# FPGA_CorePeripherals.net
KiCad netlist of a schematic drawn in Altium Designer
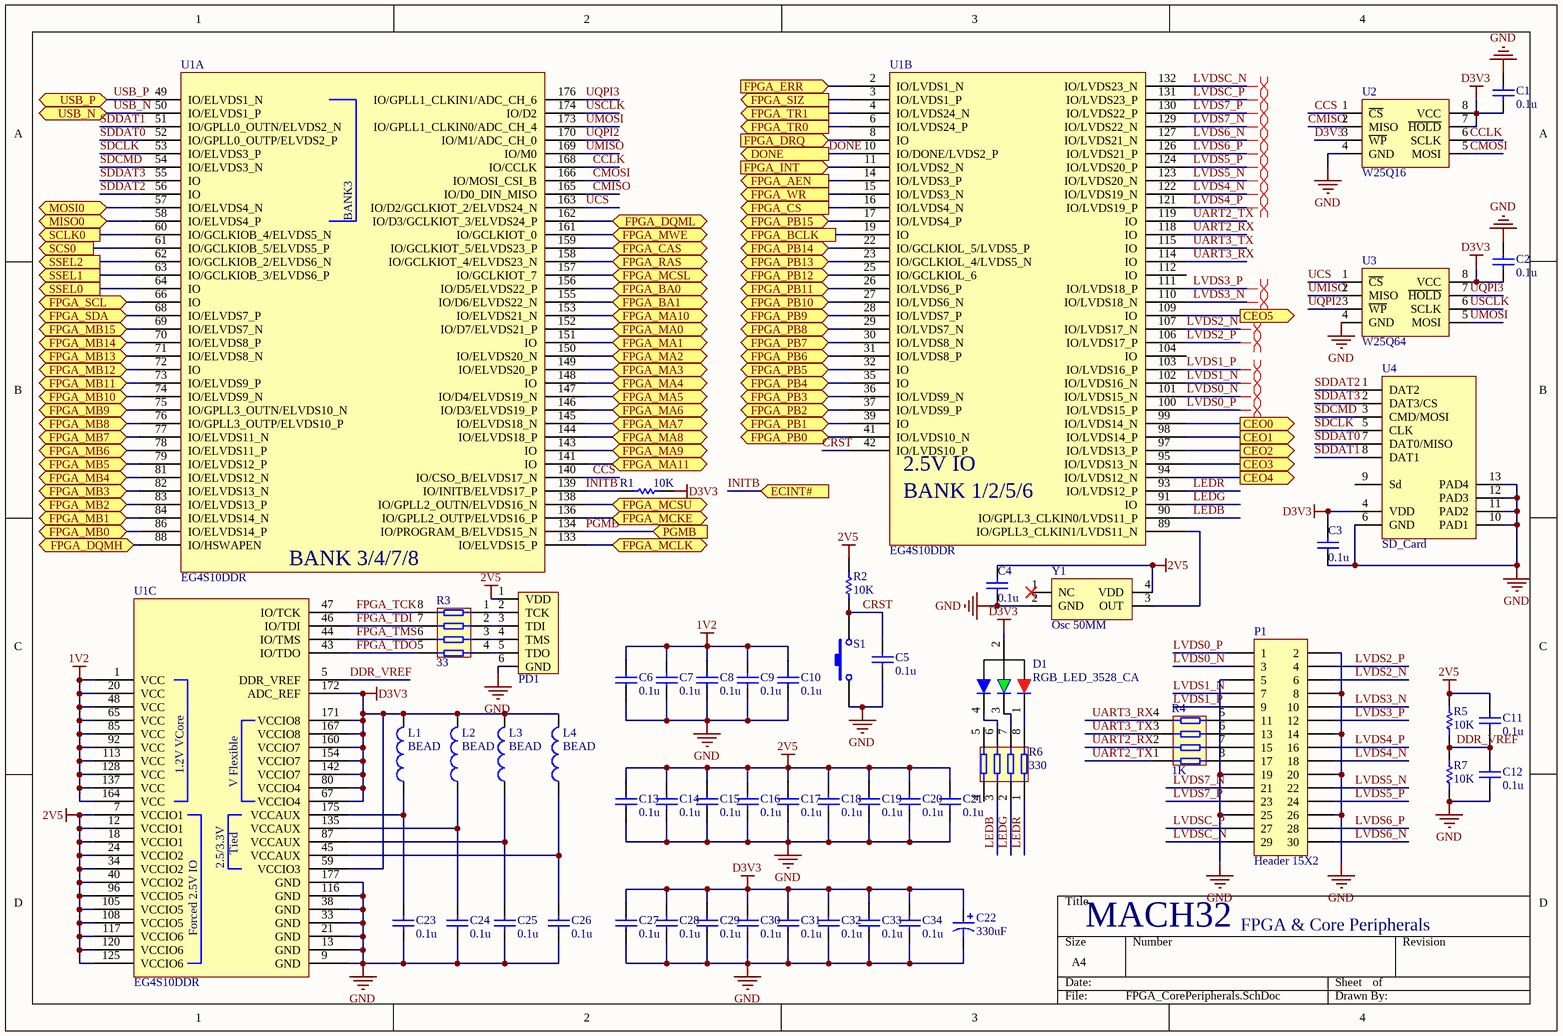
[diagram p0: FPGA_CorePeripherals.SchDoc]

(export (version "E")
  (design (tool "Eeschema 10.0.6"))
  (components
    (comp (ref "C1")
      (value "0.1u")
      (footprint "0603C")
      (description "Capacitor")
      (fields (field (name "Comment") "Cap") (field (name "PUBLISHER") "Altium Limited"))
      (libsource (lib "Miscellaneous Devices") (part "Cap"))
    )
    (comp (ref "C2")
      (value "0.1u")
      (footprint "0603C")
      (description "Capacitor")
      (fields (field (name "Comment") "Cap") (field (name "PUBLISHER") "Altium Limited"))
      (libsource (lib "Miscellaneous Devices") (part "Cap"))
    )
    (comp (ref "C3")
      (value "0.1u")
      (footprint "0603C")
      (description "Capacitor")
      (fields (field (name "Comment") "Cap") (field (name "PUBLISHER") "Altium Limited"))
      (libsource (lib "Miscellaneous Devices") (part "Cap"))
    )
    (comp (ref "C4")
      (value "0.1u")
      (footprint "0603C")
      (description "Capacitor")
      (fields (field (name "Comment") "Cap") (field (name "PUBLISHER") "Altium Limited"))
      (libsource (lib "Miscellaneous Devices") (part "Cap"))
    )
    (comp (ref "C5")
      (value "0.1u")
      (footprint "0603C")
      (description "Capacitor")
      (fields (field (name "Comment") "Cap") (field (name "PUBLISHER") "Altium Limited"))
      (libsource (lib "Miscellaneous Devices") (part "Cap"))
    )
    (comp (ref "C6")
      (value "0.1u")
      (footprint "0603C")
      (description "Capacitor")
      (fields (field (name "Comment") "Cap") (field (name "PUBLISHER") "Altium Limited"))
      (libsource (lib "Miscellaneous Devices") (part "Cap"))
    )
    (comp (ref "C7")
      (value "0.1u")
      (footprint "0603C")
      (description "Capacitor")
      (fields (field (name "Comment") "Cap") (field (name "PUBLISHER") "Altium Limited"))
      (libsource (lib "Miscellaneous Devices") (part "Cap"))
    )
    (comp (ref "C8")
      (value "0.1u")
      (footprint "0603C")
      (description "Capacitor")
      (fields (field (name "Comment") "Cap") (field (name "PUBLISHER") "Altium Limited"))
      (libsource (lib "Miscellaneous Devices") (part "Cap"))
    )
    (comp (ref "C9")
      (value "0.1u")
      (footprint "0603C")
      (description "Capacitor")
      (fields (field (name "Comment") "Cap") (field (name "PUBLISHER") "Altium Limited"))
      (libsource (lib "Miscellaneous Devices") (part "Cap"))
    )
    (comp (ref "C10")
      (value "0.1u")
      (footprint "0603C")
      (description "Capacitor")
      (fields (field (name "Comment") "Cap") (field (name "PUBLISHER") "Altium Limited"))
      (libsource (lib "Miscellaneous Devices") (part "Cap"))
    )
    (comp (ref "C11")
      (value "0.1u")
      (footprint "0603C")
      (description "Capacitor")
      (fields (field (name "Comment") "Cap") (field (name "PUBLISHER") "Altium Limited"))
      (libsource (lib "Miscellaneous Devices") (part "Cap"))
    )
    (comp (ref "C12")
      (value "0.1u")
      (footprint "0603C")
      (description "Capacitor")
      (fields (field (name "Comment") "Cap") (field (name "PUBLISHER") "Altium Limited"))
      (libsource (lib "Miscellaneous Devices") (part "Cap"))
    )
    (comp (ref "C13")
      (value "0.1u")
      (footprint "0603C")
      (description "Capacitor")
      (fields (field (name "Comment") "Cap") (field (name "PUBLISHER") "Altium Limited"))
      (libsource (lib "Miscellaneous Devices") (part "Cap"))
    )
    (comp (ref "C14")
      (value "0.1u")
      (footprint "0603C")
      (description "Capacitor")
      (fields (field (name "Comment") "Cap") (field (name "PUBLISHER") "Altium Limited"))
      (libsource (lib "Miscellaneous Devices") (part "Cap"))
    )
    (comp (ref "C15")
      (value "0.1u")
      (footprint "0603C")
      (description "Capacitor")
      (fields (field (name "Comment") "Cap") (field (name "PUBLISHER") "Altium Limited"))
      (libsource (lib "Miscellaneous Devices") (part "Cap"))
    )
    (comp (ref "C16")
      (value "0.1u")
      (footprint "0603C")
      (description "Capacitor")
      (fields (field (name "Comment") "Cap") (field (name "PUBLISHER") "Altium Limited"))
      (libsource (lib "Miscellaneous Devices") (part "Cap"))
    )
    (comp (ref "C17")
      (value "0.1u")
      (footprint "0603C")
      (description "Capacitor")
      (fields (field (name "Comment") "Cap") (field (name "PUBLISHER") "Altium Limited"))
      (libsource (lib "Miscellaneous Devices") (part "Cap"))
    )
    (comp (ref "C18")
      (value "0.1u")
      (footprint "0603C")
      (description "Capacitor")
      (fields (field (name "Comment") "Cap") (field (name "PUBLISHER") "Altium Limited"))
      (libsource (lib "Miscellaneous Devices") (part "Cap"))
    )
    (comp (ref "C19")
      (value "0.1u")
      (footprint "0603C")
      (description "Capacitor")
      (fields (field (name "Comment") "Cap") (field (name "PUBLISHER") "Altium Limited"))
      (libsource (lib "Miscellaneous Devices") (part "Cap"))
    )
    (comp (ref "C20")
      (value "0.1u")
      (footprint "0603C")
      (description "Capacitor")
      (fields (field (name "Comment") "Cap") (field (name "PUBLISHER") "Altium Limited"))
      (libsource (lib "Miscellaneous Devices") (part "Cap"))
    )
    (comp (ref "C21")
      (value "0.1u")
      (footprint "0603C")
      (description "Capacitor")
      (fields (field (name "Comment") "Cap") (field (name "PUBLISHER") "Altium Limited"))
      (libsource (lib "Miscellaneous Devices") (part "Cap"))
    )
    (comp (ref "C22")
      (value "330uF")
      (footprint "TanCap-1210")
      (description "Polarized Capacitor (Radial)")
      (fields (field (name "Comment") "330u") (field (name "PUBLISHER") "Altium Limited"))
      (libsource (lib "Miscellaneous Devices") (part "Cap Pol1"))
    )
    (comp (ref "C23")
      (value "0.1u")
      (footprint "0603C")
      (description "Capacitor")
      (fields (field (name "Comment") "Cap") (field (name "PUBLISHER") "Altium Limited"))
      (libsource (lib "Miscellaneous Devices") (part "Cap"))
    )
    (comp (ref "C24")
      (value "0.1u")
      (footprint "0603C")
      (description "Capacitor")
      (fields (field (name "Comment") "Cap") (field (name "PUBLISHER") "Altium Limited"))
      (libsource (lib "Miscellaneous Devices") (part "Cap"))
    )
    (comp (ref "C25")
      (value "0.1u")
      (footprint "0603C")
      (description "Capacitor")
      (fields (field (name "Comment") "Cap") (field (name "PUBLISHER") "Altium Limited"))
      (libsource (lib "Miscellaneous Devices") (part "Cap"))
    )
    (comp (ref "C26")
      (value "0.1u")
      (footprint "0603C")
      (description "Capacitor")
      (fields (field (name "Comment") "Cap") (field (name "PUBLISHER") "Altium Limited"))
      (libsource (lib "Miscellaneous Devices") (part "Cap"))
    )
    (comp (ref "C27")
      (value "0.1u")
      (footprint "0603C")
      (description "Capacitor")
      (fields (field (name "Comment") "Cap") (field (name "PUBLISHER") "Altium Limited"))
      (libsource (lib "Miscellaneous Devices") (part "Cap"))
    )
    (comp (ref "C28")
      (value "0.1u")
      (footprint "0603C")
      (description "Capacitor")
      (fields (field (name "Comment") "Cap") (field (name "PUBLISHER") "Altium Limited"))
      (libsource (lib "Miscellaneous Devices") (part "Cap"))
    )
    (comp (ref "C29")
      (value "0.1u")
      (footprint "0603C")
      (description "Capacitor")
      (fields (field (name "Comment") "Cap") (field (name "PUBLISHER") "Altium Limited"))
      (libsource (lib "Miscellaneous Devices") (part "Cap"))
    )
    (comp (ref "C30")
      (value "0.1u")
      (footprint "0603C")
      (description "Capacitor")
      (fields (field (name "Comment") "Cap") (field (name "PUBLISHER") "Altium Limited"))
      (libsource (lib "Miscellaneous Devices") (part "Cap"))
    )
    (comp (ref "C31")
      (value "0.1u")
      (footprint "0603C")
      (description "Capacitor")
      (fields (field (name "Comment") "Cap") (field (name "PUBLISHER") "Altium Limited"))
      (libsource (lib "Miscellaneous Devices") (part "Cap"))
    )
    (comp (ref "C32")
      (value "0.1u")
      (footprint "0603C")
      (description "Capacitor")
      (fields (field (name "Comment") "Cap") (field (name "PUBLISHER") "Altium Limited"))
      (libsource (lib "Miscellaneous Devices") (part "Cap"))
    )
    (comp (ref "C33")
      (value "0.1u")
      (footprint "0603C")
      (description "Capacitor")
      (fields (field (name "Comment") "Cap") (field (name "PUBLISHER") "Altium Limited"))
      (libsource (lib "Miscellaneous Devices") (part "Cap"))
    )
    (comp (ref "C34")
      (value "0.1u")
      (footprint "0603C")
      (description "Capacitor")
      (fields (field (name "Comment") "Cap") (field (name "PUBLISHER") "Altium Limited"))
      (libsource (lib "Miscellaneous Devices") (part "Cap"))
    )
    (comp (ref "D1")
      (value "RGB_LED_3528_CA")
      (footprint "LED3528-RGB")
      (libsource (lib "PublicSch") (part "LED3-CA"))
    )
    (comp (ref "L1")
      (value "BEAD")
      (footprint "0603C")
      (description "Inductor")
      (fields (field (name "PUBLISHER") "Altium Limited"))
      (libsource (lib "Miscellaneous Devices") (part "Inductor"))
    )
    (comp (ref "L2")
      (value "BEAD")
      (footprint "0603C")
      (description "Inductor")
      (fields (field (name "PUBLISHER") "Altium Limited"))
      (libsource (lib "Miscellaneous Devices") (part "Inductor"))
    )
    (comp (ref "L3")
      (value "BEAD")
      (footprint "0603C")
      (description "Inductor")
      (fields (field (name "PUBLISHER") "Altium Limited"))
      (libsource (lib "Miscellaneous Devices") (part "Inductor"))
    )
    (comp (ref "L4")
      (value "BEAD")
      (footprint "0603C")
      (description "Inductor")
      (fields (field (name "PUBLISHER") "Altium Limited"))
      (libsource (lib "Miscellaneous Devices") (part "Inductor"))
    )
    (comp (ref "P1")
      (value "Header 15X2")
      (footprint "BTB_1.27mm_2x10_SMT")
      (description "Header, 15-Pin, Dual row")
      (fields (field (name "PUBLISHER") "Altium Limited"))
      (libsource (lib "Miscellaneous Connectors") (part "Header 15X2"))
    )
    (comp (ref "PD1") (value "JTAG") (footprint "DBGP7") (libsource (lib "RV_AT_Ports") (part "JTAG")))
    (comp (ref "R1")
      (value "10K")
      (footprint "0603R")
      (description "Resistor")
      (fields (field (name "Comment") "Res1") (field (name "PUBLISHER") "Altium Limited"))
      (libsource (lib "Miscellaneous Devices") (part "Res1"))
    )
    (comp (ref "R2")
      (value "10K")
      (footprint "0603R")
      (description "Resistor")
      (fields (field (name "Comment") "Res1") (field (name "PUBLISHER") "Altium Limited"))
      (libsource (lib "Miscellaneous Devices") (part "Res1"))
    )
    (comp (ref "R3") (value "33") (footprint "YC164") (libsource (lib "") (part "ResPak-8P4R_2")))
    (comp (ref "R4") (value "1K") (footprint "YC164") (libsource (lib "") (part "ResPak-8P4R_1")))
    (comp (ref "R5")
      (value "10K")
      (footprint "0603R")
      (description "Resistor")
      (fields (field (name "Comment") "Res1") (field (name "PUBLISHER") "Altium Limited"))
      (libsource (lib "Miscellaneous Devices") (part "Res1"))
    )
    (comp (ref "R6") (value "330") (footprint "YC164") (libsource (lib "PublicSch") (part "ResPak-8P4R")))
    (comp (ref "R7")
      (value "10K")
      (footprint "0603R")
      (description "Resistor")
      (fields (field (name "Comment") "Res1") (field (name "PUBLISHER") "Altium Limited"))
      (libsource (lib "Miscellaneous Devices") (part "Res1"))
    )
    (comp (ref "S1")
      (value "SW-PB")
      (footprint "Switch_SMT-022S-H2.5")
      (description "Switch")
      (fields (field (name "PUBLISHER") "Altium Limited"))
      (libsource (lib "Miscellaneous Devices") (part "SW-PB"))
    )
    (comp (ref "U1")
      (value "EG4S10DDR")
      (footprint "EQFP176:EQFP176")
      (libsource (lib "EG4D20") (part "EG4S10DDR"))
    )
    (comp (ref "U2")
      (value "W25Q16")
      (footprint "SOP8N-127P600X200")
      (description "Bitstream")
      (libsource (lib "Stroage") (part "W25Qxx"))
    )
    (comp (ref "U3")
      (value "W25Q64")
      (footprint "DIP8")
      (description "Bootloader")
      (libsource (lib "Stroage") (part "W25Qxx"))
    )
    (comp (ref "U4")
      (value "SD_Card")
      (footprint "TF_self-eject")
      (libsource (lib "Stroage") (part "SD_Card"))
    )
    (comp (ref "Y1") (value "Osc 50MM") (footprint "XTAL-3225") (libsource (lib "74xLogic") (part "OSC")))
  )
  (nets
    (net (code "1") (name "/CCLK") (class "Default")
      (node (ref "U1") (pin "168") (pinfunction "IO/CCLK_168") (pintype "passive"))
      (node (ref "U2") (pin "6") (pinfunction "SCLK_6") (pintype "passive"))
    )
    (net (code "2") (name "/CCS") (class "Default")
      (node (ref "U1") (pin "140") (pinfunction "IO/CSO_B/ELVDS17_N_140") (pintype "passive"))
      (node (ref "U2") (pin "1") (pinfunction "~{CS}_1") (pintype "passive"))
    )
    (net (code "3") (name "/CEO0") (class "Default")
      (node (ref "U1") (pin "99") (pinfunction "IO/LVDS14_N_99") (pintype "passive"))
    )
    (net (code "4") (name "/CEO1") (class "Default")
      (node (ref "U1") (pin "98") (pinfunction "IO/LVDS14_P_98") (pintype "passive"))
    )
    (net (code "5") (name "/CEO2") (class "Default")
      (node (ref "U1") (pin "97") (pinfunction "IO/LVDS13_P_97") (pintype "passive"))
    )
    (net (code "6") (name "/CEO3") (class "Default")
      (node (ref "U1") (pin "95") (pinfunction "IO/LVDS13_N_95") (pintype "passive"))
    )
    (net (code "7") (name "/CEO4") (class "Default")
      (node (ref "U1") (pin "94") (pinfunction "IO/LVDS12_N_94") (pintype "passive"))
    )
    (net (code "8") (name "/CEO5") (class "Default")
      (node (ref "U1") (pin "109") (pinfunction "IO_109") (pintype "passive"))
    )
    (net (code "9") (name "/CMISO") (class "Default")
      (node (ref "U1") (pin "165") (pinfunction "IO/D0_DIN_MISO_165") (pintype "passive"))
      (node (ref "U2") (pin "2") (pinfunction "MISO_2") (pintype "passive"))
    )
    (net (code "10") (name "/CMOSI") (class "Default")
      (node (ref "U1") (pin "166") (pinfunction "IO/MOSI_CSI_B_166") (pintype "passive"))
      (node (ref "U2") (pin "5") (pinfunction "MOSI_5") (pintype "passive"))
    )
    (net (code "11") (name "/CRST") (class "Default")
      (node (ref "C5") (pin "1") (pinfunction "1_1") (pintype "passive"))
      (node (ref "R2") (pin "1") (pinfunction "1_1") (pintype "passive"))
      (node (ref "S1") (pin "2") (pinfunction "2_2") (pintype "passive"))
      (node (ref "U1") (pin "42") (pinfunction "IO/LVDS10_P_42") (pintype "passive"))
    )
    (net (code "12") (name "/DDR_VREF") (class "Default")
      (node (ref "C11") (pin "2") (pinfunction "2_2") (pintype "passive"))
      (node (ref "C12") (pin "1") (pinfunction "1_1") (pintype "passive"))
      (node (ref "R5") (pin "2") (pinfunction "2_2") (pintype "passive"))
      (node (ref "R7") (pin "1") (pinfunction "1_1") (pintype "passive"))
      (node (ref "U1") (pin "5") (pinfunction "DDR_VREF_5") (pintype "passive"))
    )
    (net (code "13") (name "/DONE") (class "Default")
      (node (ref "U1") (pin "10") (pinfunction "IO/DONE/LVDS2_P_10") (pintype "passive"))
    )
    (net (code "14") (name "/FPGA_AEN") (class "Default")
      (node (ref "U1") (pin "14") (pinfunction "IO/LVDS3_P_14") (pintype "passive"))
    )
    (net (code "15") (name "/FPGA_BA0") (class "Default")
      (node (ref "U1") (pin "156") (pinfunction "IO/D5/ELVDS22_P_156") (pintype "passive"))
    )
    (net (code "16") (name "/FPGA_BA1") (class "Default")
      (node (ref "U1") (pin "155") (pinfunction "IO/D6/ELVDS22_N_155") (pintype "passive"))
    )
    (net (code "17") (name "/FPGA_BCLK") (class "Default")
      (node (ref "U1") (pin "19") (pinfunction "IO_19") (pintype "passive"))
    )
    (net (code "18") (name "/FPGA_CAS") (class "Default")
      (node (ref "U1") (pin "159") (pinfunction "IO/GCLKIOT_5/ELVDS23_P_159") (pintype "passive"))
    )
    (net (code "19") (name "/FPGA_CS") (class "Default")
      (node (ref "U1") (pin "16") (pinfunction "IO/LVDS4_N_16") (pintype "passive"))
    )
    (net (code "20") (name "/FPGA_DQMH") (class "Default")
      (node (ref "U1") (pin "88") (pinfunction "IO/HSWAPEN_88") (pintype "passive"))
    )
    (net (code "21") (name "/FPGA_DQML") (class "Default")
      (node (ref "U1") (pin "162") (pinfunction "IO/D3/GCLKIOT_3/ELVDS24_P_162") (pintype "passive"))
    )
    (net (code "22") (name "/FPGA_DRQ") (class "Default")
      (node (ref "U1") (pin "8") (pinfunction "IO_8") (pintype "passive"))
    )
    (net (code "23") (name "/FPGA_ERR") (class "Default")
      (node (ref "U1") (pin "2") (pinfunction "IO/LVDS1_N_2") (pintype "passive"))
    )
    (net (code "24") (name "/FPGA_INT") (class "Default")
      (node (ref "U1") (pin "11") (pinfunction "IO/LVDS2_N_11") (pintype "passive"))
    )
    (net (code "25") (name "/FPGA_MA0") (class "Default")
      (node (ref "U1") (pin "152") (pinfunction "IO/D7/ELVDS21_P_152") (pintype "passive"))
    )
    (net (code "26") (name "/FPGA_MA1") (class "Default")
      (node (ref "U1") (pin "151") (pinfunction "IO_151") (pintype "passive"))
    )
    (net (code "27") (name "/FPGA_MA2") (class "Default")
      (node (ref "U1") (pin "150") (pinfunction "IO/ELVDS20_N_150") (pintype "passive"))
    )
    (net (code "28") (name "/FPGA_MA3") (class "Default")
      (node (ref "U1") (pin "149") (pinfunction "IO/ELVDS20_P_149") (pintype "passive"))
    )
    (net (code "29") (name "/FPGA_MA4") (class "Default")
      (node (ref "U1") (pin "148") (pinfunction "IO_148") (pintype "passive"))
    )
    (net (code "30") (name "/FPGA_MA5") (class "Default")
      (node (ref "U1") (pin "147") (pinfunction "IO/D4/ELVDS19_N_147") (pintype "passive"))
    )
    (net (code "31") (name "/FPGA_MA6") (class "Default")
      (node (ref "U1") (pin "146") (pinfunction "IO/D3/ELVDS19_P_146") (pintype "passive"))
    )
    (net (code "32") (name "/FPGA_MA7") (class "Default")
      (node (ref "U1") (pin "145") (pinfunction "IO/ELVDS18_N_145") (pintype "passive"))
    )
    (net (code "33") (name "/FPGA_MA8") (class "Default")
      (node (ref "U1") (pin "144") (pinfunction "IO/ELVDS18_P_144") (pintype "passive"))
    )
    (net (code "34") (name "/FPGA_MA9") (class "Default")
      (node (ref "U1") (pin "143") (pinfunction "IO_143") (pintype "passive"))
    )
    (net (code "35") (name "/FPGA_MA10") (class "Default")
      (node (ref "U1") (pin "153") (pinfunction "IO/ELVDS21_N_153") (pintype "passive"))
    )
    (net (code "36") (name "/FPGA_MA11") (class "Default")
      (node (ref "U1") (pin "141") (pinfunction "IO_141") (pintype "passive"))
    )
    (net (code "37") (name "/FPGA_MB0") (class "Default")
      (node (ref "U1") (pin "86") (pinfunction "IO/ELVDS14_P_86") (pintype "passive"))
    )
    (net (code "38") (name "/FPGA_MB1") (class "Default")
      (node (ref "U1") (pin "84") (pinfunction "IO/ELVDS14_N_84") (pintype "passive"))
    )
    (net (code "39") (name "/FPGA_MB2") (class "Default")
      (node (ref "U1") (pin "83") (pinfunction "IO/ELVDS13_P_83") (pintype "passive"))
    )
    (net (code "40") (name "/FPGA_MB3") (class "Default")
      (node (ref "U1") (pin "82") (pinfunction "IO/ELVDS13_N_82") (pintype "passive"))
    )
    (net (code "41") (name "/FPGA_MB4") (class "Default")
      (node (ref "U1") (pin "81") (pinfunction "IO/ELVDS12_N_81") (pintype "passive"))
    )
    (net (code "42") (name "/FPGA_MB5") (class "Default")
      (node (ref "U1") (pin "79") (pinfunction "IO/ELVDS12_P_79") (pintype "passive"))
    )
    (net (code "43") (name "/FPGA_MB6") (class "Default")
      (node (ref "U1") (pin "78") (pinfunction "IO/ELVDS11_P_78") (pintype "passive"))
    )
    (net (code "44") (name "/FPGA_MB7") (class "Default")
      (node (ref "U1") (pin "77") (pinfunction "IO/ELVDS11_N_77") (pintype "passive"))
    )
    (net (code "45") (name "/FPGA_MB8") (class "Default")
      (node (ref "U1") (pin "76") (pinfunction "IO/GPLL3_OUTP/ELVDS10_P_76") (pintype "passive"))
    )
    (net (code "46") (name "/FPGA_MB9") (class "Default")
      (node (ref "U1") (pin "75") (pinfunction "IO/GPLL3_OUTN/ELVDS10_N_75") (pintype "passive"))
    )
    (net (code "47") (name "/FPGA_MB10") (class "Default")
      (node (ref "U1") (pin "74") (pinfunction "IO/ELVDS9_N_74") (pintype "passive"))
    )
    (net (code "48") (name "/FPGA_MB11") (class "Default")
      (node (ref "U1") (pin "73") (pinfunction "IO/ELVDS9_P_73") (pintype "passive"))
    )
    (net (code "49") (name "/FPGA_MB12") (class "Default")
      (node (ref "U1") (pin "72") (pinfunction "IO_72") (pintype "passive"))
    )
    (net (code "50") (name "/FPGA_MB13") (class "Default")
      (node (ref "U1") (pin "71") (pinfunction "IO/ELVDS8_N_71") (pintype "passive"))
    )
    (net (code "51") (name "/FPGA_MB14") (class "Default")
      (node (ref "U1") (pin "70") (pinfunction "IO/ELVDS8_P_70") (pintype "passive"))
    )
    (net (code "52") (name "/FPGA_MB15") (class "Default")
      (node (ref "U1") (pin "69") (pinfunction "IO/ELVDS7_N_69") (pintype "passive"))
    )
    (net (code "53") (name "/FPGA_MCKE") (class "Default")
      (node (ref "U1") (pin "136") (pinfunction "IO/GPLL2_OUTP/ELVDS16_P_136") (pintype "passive"))
    )
    (net (code "54") (name "/FPGA_MCLK") (class "Default")
      (node (ref "U1") (pin "133") (pinfunction "IO/ELVDS15_P_133") (pintype "passive"))
    )
    (net (code "55") (name "/FPGA_MCSL") (class "Default")
      (node (ref "U1") (pin "157") (pinfunction "IO/GCLKIOT_7_157") (pintype "passive"))
    )
    (net (code "56") (name "/FPGA_MCSU") (class "Default")
      (node (ref "U1") (pin "138") (pinfunction "IO/GPLL2_OUTN/ELVDS16_N_138") (pintype "passive"))
    )
    (net (code "57") (name "/FPGA_MWE") (class "Default")
      (node (ref "U1") (pin "161") (pinfunction "IO/GCLKIOT_0_161") (pintype "passive"))
    )
    (net (code "58") (name "/FPGA_PB0") (class "Default")
      (node (ref "U1") (pin "41") (pinfunction "IO/LVDS10_N_41") (pintype "passive"))
    )
    (net (code "59") (name "/FPGA_PB1") (class "Default")
      (node (ref "U1") (pin "39") (pinfunction "IO_39") (pintype "passive"))
    )
    (net (code "60") (name "/FPGA_PB2") (class "Default")
      (node (ref "U1") (pin "37") (pinfunction "IO/LVDS9_P_37") (pintype "passive"))
    )
    (net (code "61") (name "/FPGA_PB3") (class "Default")
      (node (ref "U1") (pin "36") (pinfunction "IO/LVDS9_N_36") (pintype "passive"))
    )
    (net (code "62") (name "/FPGA_PB4") (class "Default")
      (node (ref "U1") (pin "35") (pinfunction "IO_35") (pintype "passive"))
    )
    (net (code "63") (name "/FPGA_PB5") (class "Default")
      (node (ref "U1") (pin "32") (pinfunction "IO_32") (pintype "passive"))
    )
    (net (code "64") (name "/FPGA_PB6") (class "Default")
      (node (ref "U1") (pin "31") (pinfunction "IO/LVDS8_P_31") (pintype "passive"))
    )
    (net (code "65") (name "/FPGA_PB7") (class "Default")
      (node (ref "U1") (pin "30") (pinfunction "IO/LVDS8_N_30") (pintype "passive"))
    )
    (net (code "66") (name "/FPGA_PB8") (class "Default")
      (node (ref "U1") (pin "29") (pinfunction "IO/LVDS7_N_29") (pintype "passive"))
    )
    (net (code "67") (name "/FPGA_PB9") (class "Default")
      (node (ref "U1") (pin "28") (pinfunction "IO/LVDS7_P_28") (pintype "passive"))
    )
    (net (code "68") (name "/FPGA_PB10") (class "Default")
      (node (ref "U1") (pin "27") (pinfunction "IO/LVDS6_N_27") (pintype "passive"))
    )
    (net (code "69") (name "/FPGA_PB11") (class "Default")
      (node (ref "U1") (pin "26") (pinfunction "IO/LVDS6_P_26") (pintype "passive"))
    )
    (net (code "70") (name "/FPGA_PB12") (class "Default")
      (node (ref "U1") (pin "25") (pinfunction "IO/GCLKIOL_6_25") (pintype "passive"))
    )
    (net (code "71") (name "/FPGA_PB13") (class "Default")
      (node (ref "U1") (pin "23") (pinfunction "IO/GCLKIOL_4/LVDS5_N_23") (pintype "passive"))
    )
    (net (code "72") (name "/FPGA_PB14") (class "Default")
      (node (ref "U1") (pin "22") (pinfunction "IO/GCLKIOL_5/LVDS5_P_22") (pintype "passive"))
    )
    (net (code "73") (name "/FPGA_PB15") (class "Default")
      (node (ref "U1") (pin "17") (pinfunction "IO/LVDS4_P_17") (pintype "passive"))
    )
    (net (code "74") (name "/FPGA_RAS") (class "Default")
      (node (ref "U1") (pin "158") (pinfunction "IO/GCLKIOT_4/ELVDS23_N_158") (pintype "passive"))
    )
    (net (code "75") (name "/FPGA_SCL") (class "Default")
      (node (ref "U1") (pin "66") (pinfunction "IO_66") (pintype "passive"))
    )
    (net (code "76") (name "/FPGA_SDA") (class "Default")
      (node (ref "U1") (pin "68") (pinfunction "IO/ELVDS7_P_68") (pintype "passive"))
    )
    (net (code "77") (name "/FPGA_SIZ") (class "Default")
      (node (ref "U1") (pin "3") (pinfunction "IO/LVDS1_P_3") (pintype "passive"))
    )
    (net (code "78") (name "/FPGA_TCK") (class "Default")
      (node (ref "R3") (pin "8") (pinfunction "8_8") (pintype "passive"))
      (node (ref "U1") (pin "47") (pinfunction "IO/TCK_47") (pintype "passive"))
    )
    (net (code "79") (name "/FPGA_TDI") (class "Default")
      (node (ref "R3") (pin "7") (pinfunction "7_7") (pintype "passive"))
      (node (ref "U1") (pin "46") (pinfunction "IO/TDI_46") (pintype "passive"))
    )
    (net (code "80") (name "/FPGA_TDO") (class "Default")
      (node (ref "R3") (pin "5") (pinfunction "5_5") (pintype "passive"))
      (node (ref "U1") (pin "43") (pinfunction "IO/TDO_43") (pintype "passive"))
    )
    (net (code "81") (name "/FPGA_TMS") (class "Default")
      (node (ref "R3") (pin "6") (pinfunction "6_6") (pintype "passive"))
      (node (ref "U1") (pin "44") (pinfunction "IO/TMS_44") (pintype "passive"))
    )
    (net (code "82") (name "/FPGA_TR0") (class "Default")
      (node (ref "U1") (pin "6") (pinfunction "IO/LVDS24_P_6") (pintype "passive"))
    )
    (net (code "83") (name "/FPGA_TR1") (class "Default")
      (node (ref "U1") (pin "4") (pinfunction "IO/LVDS24_N_4") (pintype "passive"))
    )
    (net (code "84") (name "/FPGA_WR") (class "Default")
      (node (ref "U1") (pin "15") (pinfunction "IO/LVDS3_N_15") (pintype "passive"))
    )
    (net (code "85") (name "/INITB") (class "Default")
      (node (ref "R1") (pin "1") (pinfunction "1_1") (pintype "passive"))
      (node (ref "U1") (pin "139") (pinfunction "IO/INITB/ELVDS17_P_139") (pintype "passive"))
    )
    (net (code "86") (name "/LEDB") (class "Default")
      (node (ref "R6") (pin "3") (pinfunction "3_3") (pintype "passive"))
      (node (ref "U1") (pin "90") (pinfunction "IO/GPLL3_CLKIN0/LVDS11_P_90") (pintype "passive"))
    )
    (net (code "87") (name "/LEDG") (class "Default")
      (node (ref "R6") (pin "2") (pinfunction "2_2") (pintype "passive"))
      (node (ref "U1") (pin "91") (pinfunction "IO_91") (pintype "passive"))
    )
    (net (code "88") (name "/LEDR") (class "Default")
      (node (ref "R6") (pin "1") (pinfunction "1_1") (pintype "passive"))
      (node (ref "U1") (pin "93") (pinfunction "IO/LVDS12_P_93") (pintype "passive"))
    )
    (net (code "89") (name "/LVDS0_N") (class "Default")
      (node (ref "P1") (pin "3") (pinfunction "3_3") (pintype "passive"))
      (node (ref "U1") (pin "101") (pinfunction "IO/LVDS15_N_101") (pintype "passive"))
    )
    (net (code "90") (name "/LVDS0_P") (class "Default")
      (node (ref "P1") (pin "1") (pinfunction "1_1") (pintype "passive"))
      (node (ref "U1") (pin "100") (pinfunction "IO/LVDS15_P_100") (pintype "passive"))
    )
    (net (code "91") (name "/LVDS1_N") (class "Default")
      (node (ref "P1") (pin "7") (pinfunction "7_7") (pintype "passive"))
      (node (ref "U1") (pin "102") (pinfunction "IO/LVDS16_N_102") (pintype "passive"))
    )
    (net (code "92") (name "/LVDS1_P") (class "Default")
      (node (ref "P1") (pin "9") (pinfunction "9_9") (pintype "passive"))
      (node (ref "U1") (pin "103") (pinfunction "IO/LVDS16_P_103") (pintype "passive"))
    )
    (net (code "93") (name "/LVDS2_N") (class "Default")
      (node (ref "P1") (pin "6") (pinfunction "6_6") (pintype "passive"))
      (node (ref "U1") (pin "107") (pinfunction "IO/LVDS17_N_107") (pintype "passive"))
    )
    (net (code "94") (name "/LVDS2_P") (class "Default")
      (node (ref "P1") (pin "4") (pinfunction "4_4") (pintype "passive"))
      (node (ref "U1") (pin "106") (pinfunction "IO/LVDS17_P_106") (pintype "passive"))
    )
    (net (code "95") (name "/LVDS3_N") (class "Default")
      (node (ref "P1") (pin "10") (pinfunction "10_10") (pintype "passive"))
      (node (ref "U1") (pin "110") (pinfunction "IO/LVDS18_N_110") (pintype "passive"))
    )
    (net (code "96") (name "/LVDS3_P") (class "Default")
      (node (ref "P1") (pin "12") (pinfunction "12_12") (pintype "passive"))
      (node (ref "U1") (pin "111") (pinfunction "IO/LVDS18_P_111") (pintype "passive"))
    )
    (net (code "97") (name "/LVDS4_N") (class "Default")
      (node (ref "P1") (pin "18") (pinfunction "18_18") (pintype "passive"))
      (node (ref "U1") (pin "122") (pinfunction "IO/LVDS19_N_122") (pintype "passive"))
    )
    (net (code "98") (name "/LVDS4_P") (class "Default")
      (node (ref "P1") (pin "16") (pinfunction "16_16") (pintype "passive"))
      (node (ref "U1") (pin "121") (pinfunction "IO/LVDS19_P_121") (pintype "passive"))
    )
    (net (code "99") (name "/LVDS5_N") (class "Default")
      (node (ref "P1") (pin "22") (pinfunction "22_22") (pintype "passive"))
      (node (ref "U1") (pin "123") (pinfunction "IO/LVDS20_N_123") (pintype "passive"))
    )
    (net (code "100") (name "/LVDS5_P") (class "Default")
      (node (ref "P1") (pin "24") (pinfunction "24_24") (pintype "passive"))
      (node (ref "U1") (pin "124") (pinfunction "IO/LVDS20_P_124") (pintype "passive"))
    )
    (net (code "101") (name "/LVDS6_N") (class "Default")
      (node (ref "P1") (pin "30") (pinfunction "30_30") (pintype "passive"))
      (node (ref "U1") (pin "127") (pinfunction "IO/LVDS21_N_127") (pintype "passive"))
    )
    (net (code "102") (name "/LVDS6_P") (class "Default")
      (node (ref "P1") (pin "28") (pinfunction "28_28") (pintype "passive"))
      (node (ref "U1") (pin "126") (pinfunction "IO/LVDS21_P_126") (pintype "passive"))
    )
    (net (code "103") (name "/LVDS7_N") (class "Default")
      (node (ref "P1") (pin "21") (pinfunction "21_21") (pintype "passive"))
      (node (ref "U1") (pin "129") (pinfunction "IO/LVDS22_N_129") (pintype "passive"))
    )
    (net (code "104") (name "/LVDS7_P") (class "Default")
      (node (ref "P1") (pin "23") (pinfunction "23_23") (pintype "passive"))
      (node (ref "U1") (pin "130") (pinfunction "IO/LVDS22_P_130") (pintype "passive"))
    )
    (net (code "105") (name "/LVDSC_N") (class "Default")
      (node (ref "P1") (pin "29") (pinfunction "29_29") (pintype "passive"))
      (node (ref "U1") (pin "132") (pinfunction "IO/LVDS23_N_132") (pintype "passive"))
    )
    (net (code "106") (name "/LVDSC_P") (class "Default")
      (node (ref "P1") (pin "27") (pinfunction "27_27") (pintype "passive"))
      (node (ref "U1") (pin "131") (pinfunction "IO/LVDS23_P_131") (pintype "passive"))
    )
    (net (code "107") (name "/MISO0") (class "Default")
      (node (ref "U1") (pin "58") (pinfunction "IO/ELVDS4_P_58") (pintype "passive"))
    )
    (net (code "108") (name "/MOSI0") (class "Default")
      (node (ref "U1") (pin "57") (pinfunction "IO/ELVDS4_N_57") (pintype "passive"))
    )
    (net (code "109") (name "/PGMB") (class "Default")
      (node (ref "U1") (pin "134") (pinfunction "IO/PROGRAM_B/ELVDS15_N_134") (pintype "passive"))
    )
    (net (code "110") (name "/SCLK0") (class "Default")
      (node (ref "U1") (pin "60") (pinfunction "IO/GCLKIOB_4/ELVDS5_N_60") (pintype "passive"))
    )
    (net (code "111") (name "/SCS0") (class "Default")
      (node (ref "U1") (pin "61") (pinfunction "IO/GCLKIOB_5/ELVDS5_P_61") (pintype "passive"))
    )
    (net (code "112") (name "/SDCLK") (class "Default")
      (node (ref "U1") (pin "53") (pinfunction "IO/ELVDS3_P_53") (pintype "passive"))
      (node (ref "U4") (pin "5") (pinfunction "CLK_5") (pintype "passive"))
    )
    (net (code "113") (name "/SDCMD") (class "Default")
      (node (ref "U1") (pin "54") (pinfunction "IO/ELVDS3_N_54") (pintype "passive"))
      (node (ref "U4") (pin "3") (pinfunction "CMD/MOSI_3") (pintype "passive"))
    )
    (net (code "114") (name "/SDDAT0") (class "Default")
      (node (ref "U1") (pin "52") (pinfunction "IO/GPLL0_OUTP/ELVDS2_P_52") (pintype "passive"))
      (node (ref "U4") (pin "7") (pinfunction "DAT0/MISO_7") (pintype "passive"))
    )
    (net (code "115") (name "/SDDAT1") (class "Default")
      (node (ref "U1") (pin "51") (pinfunction "IO/GPLL0_OUTN/ELVDS2_N_51") (pintype "passive"))
      (node (ref "U4") (pin "8") (pinfunction "DAT1_8") (pintype "passive"))
    )
    (net (code "116") (name "/SDDAT2") (class "Default")
      (node (ref "U1") (pin "56") (pinfunction "IO_56") (pintype "passive"))
      (node (ref "U4") (pin "1") (pinfunction "DAT2_1") (pintype "passive"))
    )
    (net (code "117") (name "/SDDAT3") (class "Default")
      (node (ref "U1") (pin "55") (pinfunction "IO_55") (pintype "passive"))
      (node (ref "U4") (pin "2") (pinfunction "DAT3/CS_2") (pintype "passive"))
    )
    (net (code "118") (name "/SSEL0") (class "Default")
      (node (ref "U1") (pin "64") (pinfunction "IO_64") (pintype "passive"))
    )
    (net (code "119") (name "/SSEL1") (class "Default")
      (node (ref "U1") (pin "63") (pinfunction "IO/GCLKIOB_3/ELVDS6_P_63") (pintype "passive"))
    )
    (net (code "120") (name "/SSEL2") (class "Default")
      (node (ref "U1") (pin "62") (pinfunction "IO/GCLKIOB_2/ELVDS6_N_62") (pintype "passive"))
    )
    (net (code "121") (name "/UART2_RX") (class "Default")
      (node (ref "R4") (pin "2") (pinfunction "2_2") (pintype "passive"))
      (node (ref "U1") (pin "118") (pinfunction "IO_118") (pintype "passive"))
    )
    (net (code "122") (name "/UART2_TX") (class "Default")
      (node (ref "R4") (pin "1") (pinfunction "1_1") (pintype "passive"))
      (node (ref "U1") (pin "119") (pinfunction "IO_119") (pintype "passive"))
    )
    (net (code "123") (name "/UART3_RX") (class "Default")
      (node (ref "R4") (pin "4") (pinfunction "4_4") (pintype "passive"))
      (node (ref "U1") (pin "114") (pinfunction "IO_114") (pintype "passive"))
    )
    (net (code "124") (name "/UART3_TX") (class "Default")
      (node (ref "R4") (pin "3") (pinfunction "3_3") (pintype "passive"))
      (node (ref "U1") (pin "115") (pinfunction "IO_115") (pintype "passive"))
    )
    (net (code "125") (name "/UCS") (class "Default")
      (node (ref "U1") (pin "163") (pinfunction "IO/D2/GCLKIOT_2/ELVDS24_N_163") (pintype "passive"))
      (node (ref "U3") (pin "1") (pinfunction "~{CS}_1") (pintype "passive"))
    )
    (net (code "126") (name "/UMISO") (class "Default")
      (node (ref "U1") (pin "169") (pinfunction "IO/M0_169") (pintype "passive"))
      (node (ref "U3") (pin "2") (pinfunction "MISO_2") (pintype "passive"))
    )
    (net (code "127") (name "/UMOSI") (class "Default")
      (node (ref "U1") (pin "173") (pinfunction "IO/GPLL1_CLKIN0/ADC_CH_4_173") (pintype "passive"))
      (node (ref "U3") (pin "5") (pinfunction "MOSI_5") (pintype "passive"))
    )
    (net (code "128") (name "/UQPI2") (class "Default")
      (node (ref "U1") (pin "170") (pinfunction "IO/M1/ADC_CH_0_170") (pintype "passive"))
      (node (ref "U3") (pin "3") (pinfunction "~{WP}_3") (pintype "passive"))
    )
    (net (code "129") (name "/UQPI3") (class "Default")
      (node (ref "U1") (pin "176") (pinfunction "IO/GPLL1_CLKIN1/ADC_CH_6_176") (pintype "passive"))
      (node (ref "U3") (pin "7") (pinfunction "~{HOLD}_7") (pintype "passive"))
    )
    (net (code "130") (name "/USB_N") (class "Default")
      (node (ref "U1") (pin "50") (pinfunction "IO/ELVDS1_P_50") (pintype "passive"))
    )
    (net (code "131") (name "/USB_P") (class "Default")
      (node (ref "U1") (pin "49") (pinfunction "IO/ELVDS1_N_49") (pintype "passive"))
    )
    (net (code "132") (name "/USCLK") (class "Default")
      (node (ref "U1") (pin "174") (pinfunction "IO/D2_174") (pintype "passive"))
      (node (ref "U3") (pin "6") (pinfunction "SCLK_6") (pintype "passive"))
    )
    (net (code "133") (name "1V2") (class "Default")
      (node (ref "C10") (pin "1") (pinfunction "1_1") (pintype "passive"))
      (node (ref "C6") (pin "1") (pinfunction "1_1") (pintype "passive"))
      (node (ref "C7") (pin "1") (pinfunction "1_1") (pintype "passive"))
      (node (ref "C8") (pin "1") (pinfunction "1_1") (pintype "passive"))
      (node (ref "C9") (pin "1") (pinfunction "1_1") (pintype "passive"))
      (node (ref "U1") (pin "1") (pinfunction "VCC_1") (pintype "passive"))
      (node (ref "U1") (pin "113") (pinfunction "VCC_113") (pintype "passive"))
      (node (ref "U1") (pin "128") (pinfunction "VCC_128") (pintype "passive"))
      (node (ref "U1") (pin "137") (pinfunction "VCC_137") (pintype "passive"))
      (node (ref "U1") (pin "164") (pinfunction "VCC_164") (pintype "passive"))
      (node (ref "U1") (pin "20") (pinfunction "VCC_20") (pintype "passive"))
      (node (ref "U1") (pin "48") (pinfunction "VCC_48") (pintype "passive"))
      (node (ref "U1") (pin "65") (pinfunction "VCC_65") (pintype "passive"))
      (node (ref "U1") (pin "85") (pinfunction "VCC_85") (pintype "passive"))
      (node (ref "U1") (pin "92") (pinfunction "VCC_92") (pintype "passive"))
    )
    (net (code "134") (name "2V5") (class "Default")
      (node (ref "C11") (pin "1") (pinfunction "1_1") (pintype "passive"))
      (node (ref "C13") (pin "1") (pinfunction "1_1") (pintype "passive"))
      (node (ref "C14") (pin "1") (pinfunction "1_1") (pintype "passive"))
      (node (ref "C15") (pin "1") (pinfunction "1_1") (pintype "passive"))
      (node (ref "C16") (pin "1") (pinfunction "1_1") (pintype "passive"))
      (node (ref "C17") (pin "1") (pinfunction "1_1") (pintype "passive"))
      (node (ref "C18") (pin "1") (pinfunction "1_1") (pintype "passive"))
      (node (ref "C19") (pin "1") (pinfunction "1_1") (pintype "passive"))
      (node (ref "C20") (pin "1") (pinfunction "1_1") (pintype "passive"))
      (node (ref "C21") (pin "1") (pinfunction "1_1") (pintype "passive"))
      (node (ref "C4") (pin "2") (pinfunction "2_2") (pintype "passive"))
      (node (ref "PD1") (pin "1") (pinfunction "VDD_1") (pintype "passive"))
      (node (ref "R2") (pin "2") (pinfunction "2_2") (pintype "passive"))
      (node (ref "R5") (pin "1") (pinfunction "1_1") (pintype "passive"))
      (node (ref "U1") (pin "105") (pinfunction "VCCIO5_105") (pintype "passive"))
      (node (ref "U1") (pin "108") (pinfunction "VCCIO5_108") (pintype "passive"))
      (node (ref "U1") (pin "117") (pinfunction "VCCIO6_117") (pintype "passive"))
      (node (ref "U1") (pin "12") (pinfunction "VCCIO1_12") (pintype "passive"))
      (node (ref "U1") (pin "120") (pinfunction "VCCIO6_120") (pintype "passive"))
      (node (ref "U1") (pin "125") (pinfunction "VCCIO6_125") (pintype "passive"))
      (node (ref "U1") (pin "18") (pinfunction "VCCIO1_18") (pintype "passive"))
      (node (ref "U1") (pin "24") (pinfunction "VCCIO2_24") (pintype "passive"))
      (node (ref "U1") (pin "34") (pinfunction "VCCIO2_34") (pintype "passive"))
      (node (ref "U1") (pin "40") (pinfunction "VCCIO2_40") (pintype "passive"))
      (node (ref "U1") (pin "7") (pinfunction "VCCIO1_7") (pintype "passive"))
      (node (ref "U1") (pin "96") (pinfunction "VCCIO5_96") (pintype "passive"))
      (node (ref "Y1") (pin "4") (pinfunction "VDD_4") (pintype "passive"))
    )
    (net (code "135") (name "D3V3") (class "Default")
      (node (ref "C1") (pin "2") (pinfunction "2_2") (pintype "passive"))
      (node (ref "C2") (pin "2") (pinfunction "2_2") (pintype "passive"))
      (node (ref "C22") (pin "1") (pinfunction "1_1") (pintype "passive"))
      (node (ref "C27") (pin "1") (pinfunction "1_1") (pintype "passive"))
      (node (ref "C28") (pin "1") (pinfunction "1_1") (pintype "passive"))
      (node (ref "C29") (pin "1") (pinfunction "1_1") (pintype "passive"))
      (node (ref "C3") (pin "2") (pinfunction "2_2") (pintype "passive"))
      (node (ref "C30") (pin "1") (pinfunction "1_1") (pintype "passive"))
      (node (ref "C31") (pin "1") (pinfunction "1_1") (pintype "passive"))
      (node (ref "C32") (pin "1") (pinfunction "1_1") (pintype "passive"))
      (node (ref "C33") (pin "1") (pinfunction "1_1") (pintype "passive"))
      (node (ref "C34") (pin "1") (pinfunction "1_1") (pintype "passive"))
      (node (ref "D1") (pin "2") (pintype "passive"))
      (node (ref "L1") (pin "2") (pinfunction "2_2") (pintype "passive"))
      (node (ref "L2") (pin "2") (pinfunction "2_2") (pintype "passive"))
      (node (ref "L3") (pin "2") (pinfunction "2_2") (pintype "passive"))
      (node (ref "L4") (pin "2") (pinfunction "2_2") (pintype "passive"))
      (node (ref "R1") (pin "2") (pinfunction "2_2") (pintype "passive"))
      (node (ref "U1") (pin "142") (pinfunction "VCCIO7_142") (pintype "passive"))
      (node (ref "U1") (pin "154") (pinfunction "VCCIO7_154") (pintype "passive"))
      (node (ref "U1") (pin "160") (pinfunction "VCCIO7_160") (pintype "passive"))
      (node (ref "U1") (pin "167") (pinfunction "VCCIO8_167") (pintype "passive"))
      (node (ref "U1") (pin "171") (pinfunction "VCCIO8_171") (pintype "passive"))
      (node (ref "U1") (pin "172") (pinfunction "ADC_REF_172") (pintype "passive"))
      (node (ref "U1") (pin "59") (pinfunction "VCCIO3_59") (pintype "passive"))
      (node (ref "U1") (pin "67") (pinfunction "VCCIO4_67") (pintype "passive"))
      (node (ref "U1") (pin "80") (pinfunction "VCCIO4_80") (pintype "passive"))
      (node (ref "U2") (pin "3") (pinfunction "~{WP}_3") (pintype "passive"))
      (node (ref "U2") (pin "7") (pinfunction "~{HOLD}_7") (pintype "passive"))
      (node (ref "U2") (pin "8") (pinfunction "VCC_8") (pintype "passive"))
      (node (ref "U3") (pin "8") (pinfunction "VCC_8") (pintype "passive"))
      (node (ref "U4") (pin "4") (pinfunction "VDD_4") (pintype "passive"))
    )
    (net (code "136") (name "GND") (class "Default")
      (node (ref "C1") (pin "1") (pinfunction "1_1") (pintype "passive"))
      (node (ref "C10") (pin "2") (pinfunction "2_2") (pintype "passive"))
      (node (ref "C12") (pin "2") (pinfunction "2_2") (pintype "passive"))
      (node (ref "C13") (pin "2") (pinfunction "2_2") (pintype "passive"))
      (node (ref "C14") (pin "2") (pinfunction "2_2") (pintype "passive"))
      (node (ref "C15") (pin "2") (pinfunction "2_2") (pintype "passive"))
      (node (ref "C16") (pin "2") (pinfunction "2_2") (pintype "passive"))
      (node (ref "C17") (pin "2") (pinfunction "2_2") (pintype "passive"))
      (node (ref "C18") (pin "2") (pinfunction "2_2") (pintype "passive"))
      (node (ref "C19") (pin "2") (pinfunction "2_2") (pintype "passive"))
      (node (ref "C2") (pin "1") (pinfunction "1_1") (pintype "passive"))
      (node (ref "C20") (pin "2") (pinfunction "2_2") (pintype "passive"))
      (node (ref "C21") (pin "2") (pinfunction "2_2") (pintype "passive"))
      (node (ref "C22") (pin "2") (pinfunction "2_2") (pintype "passive"))
      (node (ref "C23") (pin "2") (pinfunction "2_2") (pintype "passive"))
      (node (ref "C24") (pin "2") (pinfunction "2_2") (pintype "passive"))
      (node (ref "C25") (pin "2") (pinfunction "2_2") (pintype "passive"))
      (node (ref "C26") (pin "2") (pinfunction "2_2") (pintype "passive"))
      (node (ref "C27") (pin "2") (pinfunction "2_2") (pintype "passive"))
      (node (ref "C28") (pin "2") (pinfunction "2_2") (pintype "passive"))
      (node (ref "C29") (pin "2") (pinfunction "2_2") (pintype "passive"))
      (node (ref "C3") (pin "1") (pinfunction "1_1") (pintype "passive"))
      (node (ref "C30") (pin "2") (pinfunction "2_2") (pintype "passive"))
      (node (ref "C31") (pin "2") (pinfunction "2_2") (pintype "passive"))
      (node (ref "C32") (pin "2") (pinfunction "2_2") (pintype "passive"))
      (node (ref "C33") (pin "2") (pinfunction "2_2") (pintype "passive"))
      (node (ref "C34") (pin "2") (pinfunction "2_2") (pintype "passive"))
      (node (ref "C4") (pin "1") (pinfunction "1_1") (pintype "passive"))
      (node (ref "C5") (pin "2") (pinfunction "2_2") (pintype "passive"))
      (node (ref "C6") (pin "2") (pinfunction "2_2") (pintype "passive"))
      (node (ref "C7") (pin "2") (pinfunction "2_2") (pintype "passive"))
      (node (ref "C8") (pin "2") (pinfunction "2_2") (pintype "passive"))
      (node (ref "C9") (pin "2") (pinfunction "2_2") (pintype "passive"))
      (node (ref "P1") (pin "14") (pinfunction "14_14") (pintype "passive"))
      (node (ref "P1") (pin "19") (pinfunction "19_19") (pintype "passive"))
      (node (ref "P1") (pin "2") (pinfunction "2_2") (pintype "passive"))
      (node (ref "P1") (pin "20") (pinfunction "20_20") (pintype "passive"))
      (node (ref "P1") (pin "25") (pinfunction "25_25") (pintype "passive"))
      (node (ref "P1") (pin "26") (pinfunction "26_26") (pintype "passive"))
      (node (ref "P1") (pin "5") (pinfunction "5_5") (pintype "passive"))
      (node (ref "P1") (pin "8") (pinfunction "8_8") (pintype "passive"))
      (node (ref "PD1") (pin "6") (pinfunction "GND_6") (pintype "passive"))
      (node (ref "R7") (pin "2") (pinfunction "2_2") (pintype "passive"))
      (node (ref "S1") (pin "1") (pinfunction "1_1") (pintype "passive"))
      (node (ref "U1") (pin "116") (pinfunction "GND_116") (pintype "passive"))
      (node (ref "U1") (pin "13") (pinfunction "GND_13") (pintype "passive"))
      (node (ref "U1") (pin "177") (pinfunction "GND_177") (pintype "passive"))
      (node (ref "U1") (pin "21") (pinfunction "GND_21") (pintype "passive"))
      (node (ref "U1") (pin "33") (pinfunction "GND_33") (pintype "passive"))
      (node (ref "U1") (pin "38") (pinfunction "GND_38") (pintype "passive"))
      (node (ref "U1") (pin "9") (pinfunction "GND_9") (pintype "passive"))
      (node (ref "U2") (pin "4") (pinfunction "GND_4") (pintype "passive"))
      (node (ref "U3") (pin "4") (pinfunction "GND_4") (pintype "passive"))
      (node (ref "U4") (pin "10") (pinfunction "PAD1_10") (pintype "passive"))
      (node (ref "U4") (pin "11") (pinfunction "PAD2_11") (pintype "passive"))
      (node (ref "U4") (pin "12") (pinfunction "PAD3_12") (pintype "passive"))
      (node (ref "U4") (pin "13") (pinfunction "PAD4_13") (pintype "passive"))
      (node (ref "U4") (pin "6") (pinfunction "GND_6") (pintype "passive"))
      (node (ref "Y1") (pin "2") (pinfunction "GND_2") (pintype "passive"))
    )
    (net (code "137") (name "Net-(C23-Pad1)") (class "Default")
      (node (ref "C23") (pin "1") (pinfunction "1_1") (pintype "passive"))
      (node (ref "L1") (pin "1") (pinfunction "1_1") (pintype "passive"))
      (node (ref "U1") (pin "175") (pinfunction "VCCAUX_175") (pintype "passive"))
    )
    (net (code "138") (name "Net-(C24-Pad1)") (class "Default")
      (node (ref "C24") (pin "1") (pinfunction "1_1") (pintype "passive"))
      (node (ref "L2") (pin "1") (pinfunction "1_1") (pintype "passive"))
      (node (ref "U1") (pin "135") (pinfunction "VCCAUX_135") (pintype "passive"))
    )
    (net (code "139") (name "Net-(C25-Pad1)") (class "Default")
      (node (ref "C25") (pin "1") (pinfunction "1_1") (pintype "passive"))
      (node (ref "L3") (pin "1") (pinfunction "1_1") (pintype "passive"))
      (node (ref "U1") (pin "87") (pinfunction "VCCAUX_87") (pintype "passive"))
    )
    (net (code "140") (name "Net-(C26-Pad1)") (class "Default")
      (node (ref "C26") (pin "1") (pinfunction "1_1") (pintype "passive"))
      (node (ref "L4") (pin "1") (pinfunction "1_1") (pintype "passive"))
      (node (ref "U1") (pin "45") (pinfunction "VCCAUX_45") (pintype "passive"))
    )
    (net (code "141") (name "Net-(D1-Pad1)") (class "Default")
      (node (ref "D1") (pin "1") (pintype "passive"))
      (node (ref "R6") (pin "8") (pinfunction "8_8") (pintype "passive"))
    )
    (net (code "142") (name "Net-(D1-Pad3)") (class "Default")
      (node (ref "D1") (pin "3") (pintype "passive"))
      (node (ref "R6") (pin "7") (pinfunction "7_7") (pintype "passive"))
    )
    (net (code "143") (name "Net-(D1-Pad4)") (class "Default")
      (node (ref "D1") (pin "4") (pintype "passive"))
      (node (ref "R6") (pin "6") (pinfunction "6_6") (pintype "passive"))
    )
    (net (code "144") (name "Net-(P1-Pad11)") (class "Default")
      (node (ref "P1") (pin "11") (pinfunction "11_11") (pintype "passive"))
      (node (ref "R4") (pin "5") (pinfunction "5_5") (pintype "passive"))
    )
    (net (code "145") (name "Net-(P1-Pad13)") (class "Default")
      (node (ref "P1") (pin "13") (pinfunction "13_13") (pintype "passive"))
      (node (ref "R4") (pin "6") (pinfunction "6_6") (pintype "passive"))
    )
    (net (code "146") (name "Net-(P1-Pad15)") (class "Default")
      (node (ref "P1") (pin "15") (pinfunction "15_15") (pintype "passive"))
      (node (ref "R4") (pin "7") (pinfunction "7_7") (pintype "passive"))
    )
    (net (code "147") (name "Net-(P1-Pad17)") (class "Default")
      (node (ref "P1") (pin "17") (pinfunction "17_17") (pintype "passive"))
      (node (ref "R4") (pin "8") (pinfunction "8_8") (pintype "passive"))
    )
    (net (code "148") (name "Net-(PD1-TCK)") (class "Default")
      (node (ref "PD1") (pin "2") (pinfunction "TCK_2") (pintype "passive"))
      (node (ref "R3") (pin "1") (pinfunction "1_1") (pintype "passive"))
    )
    (net (code "149") (name "Net-(PD1-TDI)") (class "Default")
      (node (ref "PD1") (pin "3") (pinfunction "TDI_3") (pintype "passive"))
      (node (ref "R3") (pin "2") (pinfunction "2_2") (pintype "passive"))
    )
    (net (code "150") (name "Net-(PD1-TDO)") (class "Default")
      (node (ref "PD1") (pin "5") (pinfunction "TDO_5") (pintype "passive"))
      (node (ref "R3") (pin "4") (pinfunction "4_4") (pintype "passive"))
    )
    (net (code "151") (name "Net-(PD1-TMS)") (class "Default")
      (node (ref "PD1") (pin "4") (pinfunction "TMS_4") (pintype "passive"))
      (node (ref "R3") (pin "3") (pinfunction "3_3") (pintype "passive"))
    )
    (net (code "152") (name "Net-(U1B-IO{slash}GPLL3_CLKIN1{slash}LVDS11_N)") (class "Default")
      (node (ref "U1") (pin "89") (pinfunction "IO/GPLL3_CLKIN1/LVDS11_N_89") (pintype "passive"))
      (node (ref "Y1") (pin "3") (pinfunction "OUT_3") (pintype "passive"))
    )
    (net (code "153") (name "unconnected-(R6-Pad4)") (class "Default")
      (node (ref "R6") (pin "4") (pinfunction "4_4") (pintype "passive"))
    )
    (net (code "154") (name "unconnected-(R6-Pad5)") (class "Default")
      (node (ref "R6") (pin "5") (pinfunction "5_5") (pintype "passive"))
    )
    (net (code "155") (name "unconnected-(U1B-IO-Pad104)") (class "Default")
      (node (ref "U1") (pin "104") (pinfunction "IO_104") (pintype "passive"))
    )
    (net (code "156") (name "unconnected-(U1B-IO-Pad112)") (class "Default")
      (node (ref "U1") (pin "112") (pinfunction "IO_112") (pintype "passive"))
    )
    (net (code "157") (name "unconnected-(U4-Sd-Pad9)") (class "Default")
      (node (ref "U4") (pin "9") (pinfunction "Sd_9") (pintype "passive"))
    )
    (net (code "158") (name "unconnected-(Y1-NC-Pad1)") (class "Default")
      (node (ref "Y1") (pin "1") (pinfunction "NC_1") (pintype "passive+no_connect"))
    )
  )
)
